# WSN.net
KiCad netlist of a schematic drawn in Altium Designer
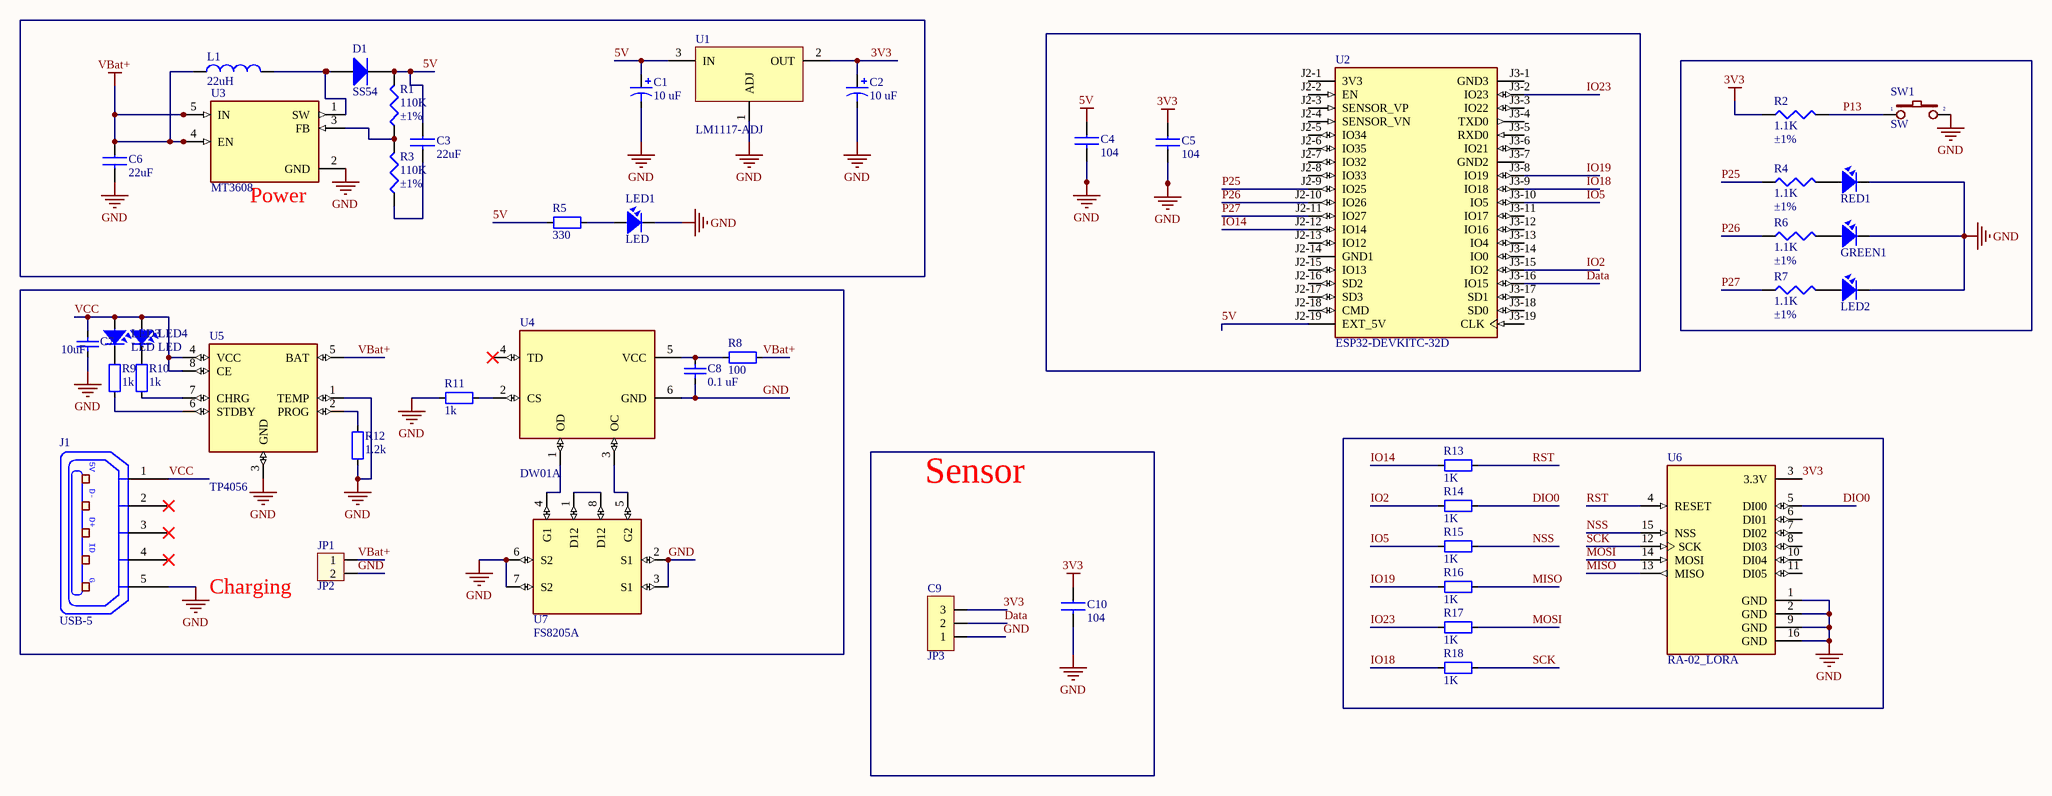
[diagram p0: WSN.SchDoc]

(export (version "E")
  (design (tool "Eeschema 10.0.6"))
  (components
    (comp (ref "C1")
      (value "10 uF")
      (footprint "C3MM")
      (description "Polarized Capacitor (Axial)")
      (fields (field (name "PUBLISHER") "Altium Limited"))
      (libsource (lib "My Library") (part "Cap Pol"))
    )
    (comp (ref "C2")
      (value "10 uF")
      (footprint "C3MM")
      (description "Polarized Capacitor (Axial)")
      (fields (field (name "PUBLISHER") "Altium Limited"))
      (libsource (lib "My Library") (part "Cap Pol"))
    )
    (comp (ref "C3")
      (value "22uF")
      (footprint "CAP0603")
      (description "CAP CER 30PF 50V NPO 0603")
      (fields
        (field (name "MANUFACTURER") "Yageo")
        (field (name "MANUFACTURER PART NUMBER") "CC0603JRNPO9BN300")
      )
      (libsource (lib "KhanhBK_SCH_Lib_6") (part "CC0603JRNPO9BN300"))
    )
    (comp (ref "C4")
      (value "104")
      (footprint "CAP0603")
      (description "CAP CER 30PF 50V NPO 0603")
      (fields
        (field (name "MANUFACTURER") "Yageo")
        (field (name "MANUFACTURER PART NUMBER") "CC0603JRNPO9BN300")
      )
      (libsource (lib "KhanhBK_SCH_Lib_6") (part "CC0603JRNPO9BN300"))
    )
    (comp (ref "C5")
      (value "104")
      (footprint "CAP0603")
      (description "CAP CER 30PF 50V NPO 0603")
      (fields
        (field (name "MANUFACTURER") "Yageo")
        (field (name "MANUFACTURER PART NUMBER") "CC0603JRNPO9BN300")
      )
      (libsource (lib "KhanhBK_SCH_Lib_6") (part "CC0603JRNPO9BN300"))
    )
    (comp (ref "C6")
      (value "22uF")
      (footprint "CAP0603")
      (description "CAP CER 30PF 50V NPO 0603")
      (fields
        (field (name "MANUFACTURER") "Yageo")
        (field (name "MANUFACTURER PART NUMBER") "CC0603JRNPO9BN300")
      )
      (libsource (lib "KhanhBK_SCH_Lib_6") (part "CC0603JRNPO9BN300"))
    )
    (comp (ref "C7")
      (value "10uF")
      (footprint "CAP_0805")
      (description "Capacitor")
      (fields (field (name "PUBLISHER") "Altium Limited"))
      (libsource (lib "My Library") (part "CapSMD"))
    )
    (comp (ref "C8")
      (value "0.1 uF")
      (footprint "CAP_0805")
      (description "Capacitor")
      (fields (field (name "PUBLISHER") "Altium Limited"))
      (libsource (lib "My Library") (part "CapSMD"))
    )
    (comp (ref "C9")
      (value "JP3")
      (footprint "JP3-C1T")
      (description "WR-PHD 2.54 mm Angled Socket Header")
      (fields
        (field (name "MANUFACTURER") "Würth Elektronik eiSos GmbH")
        (field (name "PARTNO") "613003143121")
        (field (name "CREATED BY") "Karrer Zheng")
      )
      (libsource (lib "KhanhBK_SCH_Library_1") (part "JP3"))
    )
    (comp (ref "C10")
      (value "104")
      (footprint "CAP0603")
      (description "CAP CER 30PF 50V NPO 0603")
      (fields
        (field (name "MANUFACTURER") "Yageo")
        (field (name "MANUFACTURER PART NUMBER") "CC0603JRNPO9BN300")
      )
      (libsource (lib "KhanhBK_SCH_Lib_6") (part "CC0603JRNPO9BN300"))
    )
    (comp (ref "D1")
      (value "SS54")
      (footprint "DIODE/POW/1A")
      (description "Diode Power")
      (fields (field (name "PUBLISHER") "Altium Limited"))
      (libsource (lib "Cty1") (part "Diode Power"))
    )
    (comp (ref "GREEN1")
      (value "LED")
      (footprint "LED-3MM-GREEN")
      (description "LED Single colour Green and Red")
      (libsource (lib "KhanhBK_SCH_Library_1") (part "LED"))
    )
    (comp (ref "J1")
      (value "USB-5")
      (footprint "USB-M1")
      (fields
        (field (name "MANUFACTURER") "FCI")
        (field (name "MANUFACTURER PART NUMBER") "10118193-0001LF")
        (field (name ".CREATOR") "MM")
        (field (name ".CHECKED PCB") "RF")
        (field (name ".CHECKED SCH") "MM")
      )
      (libsource (lib "My Library") (part "USB-5"))
    )
    (comp (ref "JP1")
      (value "JP2")
      (footprint "CON2")
      (description "Connector 2")
      (libsource (lib "My Library") (part "Con2"))
    )
    (comp (ref "L1")
      (value "22uH")
      (footprint "IND_400_500_212x114_SMD")
      (description "1mH Shielded Wirewound Inductor 600mA 1.82Ohm Max Nonstandard")
      (fields (field (name "MANUFACTURER") "Coilcraft") (field (name "MANUFACTURER PART NUMBER") "74477030"))
      (libsource (lib "Altium_Lib_by_KhueNguyenCreator") (part "IND_1mH-0.6A-20%-SMD"))
    )
    (comp (ref "LED1")
      (value "LED")
      (footprint "LED-0805-Red")
      (description "LED Single colour Green and Red")
      (libsource (lib "My Library") (part "LED"))
    )
    (comp (ref "LED2")
      (value "LED")
      (footprint "LED-3MM-YELLOW")
      (description "LED Single colour Green and Red")
      (libsource (lib "KhanhBK_SCH_Library_1") (part "LED"))
    )
    (comp (ref "LED3")
      (value "LED")
      (footprint "LED-0805-Green")
      (description "LED Single colour Green and Red")
      (libsource (lib "My Library") (part "LED"))
    )
    (comp (ref "LED4")
      (value "LED")
      (footprint "LED-0805-Red")
      (description "LED Single colour Green and Red")
      (libsource (lib "My Library") (part "LED"))
    )
    (comp (ref "R1")
      (value "110K")
      (footprint "RES0603")
      (description "RES SMD 1K OHM 1% 1/10W 0603")
      (fields
        (field (name "MANUFACTURER") "Yageo")
        (field (name "MANUFACTURER PART NUMBER") "RT0603FRD071KL")
        (field (name "TOLERANCE") "±1%")
      )
      (libsource (lib "KhanhBK_SCH_Lib_6") (part "RT0603FRD071KL"))
    )
    (comp (ref "R2")
      (value "1.1K")
      (footprint "RES0603")
      (description "RES SMD 1K OHM 1% 1/10W 0603")
      (fields
        (field (name "MANUFACTURER") "Yageo")
        (field (name "MANUFACTURER PART NUMBER") "RT0603FRD071KL")
        (field (name "TOLERANCE") "±1%")
      )
      (libsource (lib "KhanhBK_SCH_Lib_6") (part "RT0603FRD071KL"))
    )
    (comp (ref "R3")
      (value "110K")
      (footprint "RES0603")
      (description "RES SMD 1K OHM 1% 1/10W 0603")
      (fields
        (field (name "MANUFACTURER") "Yageo")
        (field (name "MANUFACTURER PART NUMBER") "RT0603FRD071KL")
        (field (name "TOLERANCE") "±1%")
      )
      (libsource (lib "KhanhBK_SCH_Lib_6") (part "RT0603FRD071KL"))
    )
    (comp (ref "R4")
      (value "1.1K")
      (footprint "RES0603")
      (description "RES SMD 1K OHM 1% 1/10W 0603")
      (fields
        (field (name "MANUFACTURER") "Yageo")
        (field (name "MANUFACTURER PART NUMBER") "RT0603FRD071KL")
        (field (name "TOLERANCE") "±1%")
      )
      (libsource (lib "KhanhBK_SCH_Lib_6") (part "RT0603FRD071KL"))
    )
    (comp (ref "R5")
      (value "330")
      (footprint "RES-SMD-0805")
      (description "Resistor")
      (fields
        (field (name "MANUFACTURER") "Generic Components")
        (field (name "PUBLISHER") "Altium Hobart Technology Centre")
      )
      (libsource (lib "My Library") (part "Resistor - SMD"))
    )
    (comp (ref "R6")
      (value "1.1K")
      (footprint "RES0603")
      (description "RES SMD 1K OHM 1% 1/10W 0603")
      (fields
        (field (name "MANUFACTURER") "Yageo")
        (field (name "MANUFACTURER PART NUMBER") "RT0603FRD071KL")
        (field (name "TOLERANCE") "±1%")
      )
      (libsource (lib "KhanhBK_SCH_Lib_6") (part "RT0603FRD071KL"))
    )
    (comp (ref "R7")
      (value "1.1K")
      (footprint "RES0603")
      (description "RES SMD 1K OHM 1% 1/10W 0603")
      (fields
        (field (name "MANUFACTURER") "Yageo")
        (field (name "MANUFACTURER PART NUMBER") "RT0603FRD071KL")
        (field (name "TOLERANCE") "±1%")
      )
      (libsource (lib "KhanhBK_SCH_Lib_6") (part "RT0603FRD071KL"))
    )
    (comp (ref "R8")
      (value "100")
      (footprint "RES-SMD-0805")
      (description "Resistor")
      (fields
        (field (name "MANUFACTURER") "Generic Components")
        (field (name "PUBLISHER") "Altium Hobart Technology Centre")
      )
      (libsource (lib "My Library") (part "Resistor - SMD"))
    )
    (comp (ref "R9")
      (value "1k")
      (footprint "RES-SMD-0805")
      (description "Resistor")
      (fields
        (field (name "MANUFACTURER") "Generic Components")
        (field (name "PUBLISHER") "Altium Hobart Technology Centre")
      )
      (libsource (lib "My Library") (part "Resistor - SMD"))
    )
    (comp (ref "R10")
      (value "1k")
      (footprint "RES-SMD-0805")
      (description "Resistor")
      (fields
        (field (name "MANUFACTURER") "Generic Components")
        (field (name "PUBLISHER") "Altium Hobart Technology Centre")
      )
      (libsource (lib "My Library") (part "Resistor - SMD"))
    )
    (comp (ref "R11")
      (value "1k")
      (footprint "RES-SMD-0805")
      (description "Resistor")
      (fields
        (field (name "MANUFACTURER") "Generic Components")
        (field (name "PUBLISHER") "Altium Hobart Technology Centre")
      )
      (libsource (lib "My Library") (part "Resistor - SMD"))
    )
    (comp (ref "R12")
      (value "1.2k")
      (footprint "RES-SMD-0805")
      (description "Resistor")
      (fields
        (field (name "MANUFACTURER") "Generic Components")
        (field (name "PUBLISHER") "Altium Hobart Technology Centre")
      )
      (libsource (lib "My Library") (part "Resistor - SMD"))
    )
    (comp (ref "R13")
      (value "1K")
      (footprint "RES-SMD-0805")
      (description "Resistor")
      (fields
        (field (name "MANUFACTURER") "Generic Components")
        (field (name "PUBLISHER") "Altium Hobart Technology Centre")
      )
      (libsource (lib "My Library") (part "Resistor - SMD"))
    )
    (comp (ref "R14")
      (value "1K")
      (footprint "RES-SMD-0805")
      (description "Resistor")
      (fields
        (field (name "MANUFACTURER") "Generic Components")
        (field (name "PUBLISHER") "Altium Hobart Technology Centre")
      )
      (libsource (lib "My Library") (part "Resistor - SMD"))
    )
    (comp (ref "R15")
      (value "1K")
      (footprint "RES-SMD-0805")
      (description "Resistor")
      (fields
        (field (name "MANUFACTURER") "Generic Components")
        (field (name "PUBLISHER") "Altium Hobart Technology Centre")
      )
      (libsource (lib "My Library") (part "Resistor - SMD"))
    )
    (comp (ref "R16")
      (value "1K")
      (footprint "RES-SMD-0805")
      (description "Resistor")
      (fields
        (field (name "MANUFACTURER") "Generic Components")
        (field (name "PUBLISHER") "Altium Hobart Technology Centre")
      )
      (libsource (lib "My Library") (part "Resistor - SMD"))
    )
    (comp (ref "R17")
      (value "1K")
      (footprint "RES-SMD-0805")
      (description "Resistor")
      (fields
        (field (name "MANUFACTURER") "Generic Components")
        (field (name "PUBLISHER") "Altium Hobart Technology Centre")
      )
      (libsource (lib "My Library") (part "Resistor - SMD"))
    )
    (comp (ref "R18")
      (value "1K")
      (footprint "RES-SMD-0805")
      (description "Resistor")
      (fields
        (field (name "MANUFACTURER") "Generic Components")
        (field (name "PUBLISHER") "Altium Hobart Technology Centre")
      )
      (libsource (lib "My Library") (part "Resistor - SMD"))
    )
    (comp (ref "RED1")
      (value "LED")
      (footprint "LED-3MM-RED")
      (description "LED Single colour Green and Red")
      (libsource (lib "KhanhBK_SCH_Library_1") (part "LED"))
    )
    (comp (ref "SW1")
      (value "SW")
      (footprint "SW1-SMD")
      (description "Switch button 2 pin")
      (libsource (lib "KhanhBK_SCH_Library_1") (part "SW2"))
    )
    (comp (ref "U1")
      (value "LM1117-ADJ")
      (footprint "LM1117-SOP")
      (description "800mA Low-Dropout Linear Regulator")
      (fields (field (name "CREATOR") "Nguyen Ba Bien"))
      (libsource (lib "My Library") (part "LM1117-ADJ"))
    )
    (comp (ref "U2")
      (value "ESP32-DEVKITC-32D")
      (footprint "MODULE_ESP32-DEVKITC-32D")
      (description "WiFi Development Tools (802.11) ESP32 General Development Kit, ESP32-WROOM-32D on the board")
      (fields (field (name "MF") "Espressif Systems"))
      (libsource (lib "ESP32-DEVKITC-32D") (part "ESP32-DEVKITC-32D"))
    )
    (comp (ref "U3")
      (value "MT3608")
      (footprint "SOT95P280X145-6N")
      (description "High Efficiency 1.2MHz2A Step Up Converter")
      (fields (field (name "MF") "Aerosemi Technology Co., Ltd"))
      (libsource (lib "MT3608") (part "MT3608"))
    )
    (comp (ref "U4")
      (value "DW01A")
      (footprint "SOT23-6")
      (description "One Cell Lithium-ion/Polymer Battery Protection IC")
      (libsource (lib "My Library") (part "DW01A"))
    )
    (comp (ref "U5")
      (value "TP4056")
      (footprint "TP4056")
      (description "Complete single cell Li-Ion battery with a constant current / constant voltage linear charger")
      (libsource (lib "My Library") (part "TP4056"))
    )
    (comp (ref "U6")
      (value "RA-02_LORA")
      (footprint "MODULE_RA-02_LORA")
      (description "Ra-02 LoRa RF M5Stack Platform Evaluation Expansion Board")
      (libsource (lib "RA-02_LORA (1)") (part "RA-02_LORA"))
    )
    (comp (ref "U7") (value "FS8205A") (footprint "FS8205A") (libsource (lib "My Library") (part "FS8205A")))
  )
  (nets
    (net (code "1") (name "/DIO0") (class "Default")
      (node (ref "R14") (pin "2") (pinfunction "2_2") (pintype "passive"))
      (node (ref "U6") (pin "5") (pinfunction "DI00_5") (pintype "bidirectional"))
    )
    (net (code "2") (name "/Data") (class "Default")
      (node (ref "C9") (pin "2") (pinfunction "2_2") (pintype "passive"))
      (node (ref "U2") (pin "J3-16") (pinfunction "IO15_J3-16") (pintype "bidirectional"))
    )
    (net (code "3") (name "/IO2") (class "Default")
      (node (ref "R14") (pin "1") (pinfunction "1_1") (pintype "passive"))
      (node (ref "U2") (pin "J3-15") (pinfunction "IO2_J3-15") (pintype "bidirectional"))
    )
    (net (code "4") (name "/IO5") (class "Default")
      (node (ref "R15") (pin "1") (pinfunction "1_1") (pintype "passive"))
      (node (ref "U2") (pin "J3-10") (pinfunction "IO5_J3-10") (pintype "bidirectional"))
    )
    (net (code "5") (name "/IO14") (class "Default")
      (node (ref "R13") (pin "1") (pinfunction "1_1") (pintype "passive"))
      (node (ref "U2") (pin "J2-12") (pinfunction "IO14_J2-12") (pintype "bidirectional"))
    )
    (net (code "6") (name "/IO18") (class "Default")
      (node (ref "R18") (pin "1") (pinfunction "1_1") (pintype "passive"))
      (node (ref "U2") (pin "J3-9") (pinfunction "IO18_J3-9") (pintype "bidirectional"))
    )
    (net (code "7") (name "/IO19") (class "Default")
      (node (ref "R16") (pin "1") (pinfunction "1_1") (pintype "passive"))
      (node (ref "U2") (pin "J3-8") (pinfunction "IO19_J3-8") (pintype "bidirectional"))
    )
    (net (code "8") (name "/IO23") (class "Default")
      (node (ref "R17") (pin "1") (pinfunction "1_1") (pintype "passive"))
      (node (ref "U2") (pin "J3-2") (pinfunction "IO23_J3-2") (pintype "bidirectional"))
    )
    (net (code "9") (name "/MISO") (class "Default")
      (node (ref "R16") (pin "2") (pinfunction "2_2") (pintype "passive"))
      (node (ref "U6") (pin "13") (pinfunction "MISO_13") (pintype "output"))
    )
    (net (code "10") (name "/MOSI") (class "Default")
      (node (ref "R17") (pin "2") (pinfunction "2_2") (pintype "passive"))
      (node (ref "U6") (pin "14") (pinfunction "MOSI_14") (pintype "input"))
    )
    (net (code "11") (name "/NSS") (class "Default")
      (node (ref "R15") (pin "2") (pinfunction "2_2") (pintype "passive"))
      (node (ref "U6") (pin "15") (pinfunction "NSS_15") (pintype "input"))
    )
    (net (code "12") (name "/P13") (class "Default")
      (node (ref "R2") (pin "2") (pinfunction "2_2") (pintype "passive"))
      (node (ref "SW1") (pin "1") (pinfunction "1_1") (pintype "passive"))
    )
    (net (code "13") (name "/P25") (class "Default")
      (node (ref "R4") (pin "1") (pinfunction "1_1") (pintype "passive"))
      (node (ref "U2") (pin "J2-9") (pinfunction "IO25_J2-9") (pintype "bidirectional"))
    )
    (net (code "14") (name "/P26") (class "Default")
      (node (ref "R6") (pin "1") (pinfunction "1_1") (pintype "passive"))
      (node (ref "U2") (pin "J2-10") (pinfunction "IO26_J2-10") (pintype "bidirectional"))
    )
    (net (code "15") (name "/P27") (class "Default")
      (node (ref "R7") (pin "1") (pinfunction "1_1") (pintype "passive"))
      (node (ref "U2") (pin "J2-11") (pinfunction "IO27_J2-11") (pintype "bidirectional"))
    )
    (net (code "16") (name "/RST") (class "Default")
      (node (ref "R13") (pin "2") (pinfunction "2_2") (pintype "passive"))
      (node (ref "U6") (pin "4") (pinfunction "RESET_4") (pintype "input"))
    )
    (net (code "17") (name "/SCK") (class "Default")
      (node (ref "R18") (pin "2") (pinfunction "2_2") (pintype "passive"))
      (node (ref "U6") (pin "12") (pinfunction "SCK_12") (pintype "input"))
    )
    (net (code "18") (name "/VCC") (class "Default")
      (node (ref "C7") (pin "2") (pinfunction "2_2") (pintype "passive"))
      (node (ref "J1") (pin "1") (pinfunction "P1_1") (pintype "passive"))
      (node (ref "LED3") (pin "1") (pinfunction "1_1") (pintype "passive"))
      (node (ref "LED4") (pin "1") (pinfunction "1_1") (pintype "passive"))
      (node (ref "U5") (pin "4") (pinfunction "VCC_4") (pintype "bidirectional"))
      (node (ref "U5") (pin "8") (pinfunction "CE_8") (pintype "bidirectional"))
    )
    (net (code "19") (name "3V3") (class "Default")
      (node (ref "C10") (pin "1") (pinfunction "1_1") (pintype "passive"))
      (node (ref "C2") (pin "1") (pinfunction "1_1") (pintype "passive"))
      (node (ref "C5") (pin "1") (pinfunction "1_1") (pintype "passive"))
      (node (ref "C9") (pin "3") (pinfunction "3_3") (pintype "passive"))
      (node (ref "R2") (pin "1") (pinfunction "1_1") (pintype "passive"))
      (node (ref "U1") (pin "2") (pinfunction "OUT_2") (pintype "passive"))
      (node (ref "U6") (pin "3") (pinfunction "3.3V_3") (pintype "power_in"))
    )
    (net (code "20") (name "5V") (class "Default")
      (node (ref "C1") (pin "1") (pinfunction "1_1") (pintype "passive"))
      (node (ref "C3") (pin "1") (pinfunction "1_1") (pintype "passive"))
      (node (ref "C4") (pin "1") (pinfunction "1_1") (pintype "passive"))
      (node (ref "D1") (pin "2") (pinfunction "K_2") (pintype "passive"))
      (node (ref "R1") (pin "2") (pinfunction "2_2") (pintype "passive"))
      (node (ref "R5") (pin "1") (pinfunction "1_1") (pintype "passive"))
      (node (ref "U1") (pin "3") (pinfunction "IN_3") (pintype "passive"))
      (node (ref "U2") (pin "J2-19") (pinfunction "EXT_5V_J2-19") (pintype "power_in"))
    )
    (net (code "21") (name "GND") (class "Default")
      (node (ref "C1") (pin "2") (pinfunction "2_2") (pintype "passive"))
      (node (ref "C10") (pin "2") (pinfunction "2_2") (pintype "passive"))
      (node (ref "C2") (pin "2") (pinfunction "2_2") (pintype "passive"))
      (node (ref "C4") (pin "2") (pinfunction "2_2") (pintype "passive"))
      (node (ref "C5") (pin "2") (pinfunction "2_2") (pintype "passive"))
      (node (ref "C6") (pin "2") (pinfunction "2_2") (pintype "passive"))
      (node (ref "C7") (pin "1") (pinfunction "1_1") (pintype "passive"))
      (node (ref "C8") (pin "1") (pinfunction "1_1") (pintype "passive"))
      (node (ref "C9") (pin "1") (pinfunction "1_1") (pintype "passive"))
      (node (ref "GREEN1") (pin "2") (pinfunction "2_2") (pintype "passive"))
      (node (ref "J1") (pin "5") (pinfunction "P5_5") (pintype "passive"))
      (node (ref "JP1") (pin "2") (pinfunction "2_2") (pintype "passive"))
      (node (ref "LED1") (pin "2") (pinfunction "2_2") (pintype "passive"))
      (node (ref "LED2") (pin "2") (pinfunction "2_2") (pintype "passive"))
      (node (ref "R11") (pin "1") (pinfunction "1_1") (pintype "passive"))
      (node (ref "R12") (pin "1") (pinfunction "1_1") (pintype "passive"))
      (node (ref "RED1") (pin "2") (pinfunction "2_2") (pintype "passive"))
      (node (ref "SW1") (pin "2") (pinfunction "2_2") (pintype "passive"))
      (node (ref "U1") (pin "1") (pinfunction "ADJ_1") (pintype "passive"))
      (node (ref "U3") (pin "2") (pinfunction "GND_2") (pintype "power_in"))
      (node (ref "U4") (pin "6") (pinfunction "GND_6") (pintype "power_in"))
      (node (ref "U5") (pin "1") (pinfunction "TEMP_1") (pintype "bidirectional"))
      (node (ref "U5") (pin "3") (pinfunction "GND_3") (pintype "bidirectional"))
      (node (ref "U6") (pin "1") (pinfunction "GND_1") (pintype "power_in"))
      (node (ref "U6") (pin "16") (pinfunction "GND_16") (pintype "power_in"))
      (node (ref "U6") (pin "2") (pinfunction "GND_2") (pintype "power_in"))
      (node (ref "U6") (pin "9") (pinfunction "GND_9") (pintype "power_in"))
      (node (ref "U7") (pin "2") (pinfunction "S1_2") (pintype "bidirectional"))
      (node (ref "U7") (pin "3") (pinfunction "S1_3") (pintype "bidirectional"))
      (node (ref "U7") (pin "6") (pinfunction "S2_6") (pintype "bidirectional"))
      (node (ref "U7") (pin "7") (pinfunction "S2_7") (pintype "bidirectional"))
    )
    (net (code "22") (name "Net-(C3-Pad2)") (class "Default")
      (node (ref "C3") (pin "2") (pinfunction "2_2") (pintype "passive"))
      (node (ref "R3") (pin "1") (pinfunction "1_1") (pintype "passive"))
    )
    (net (code "23") (name "Net-(D1-A)") (class "Default")
      (node (ref "D1") (pin "1") (pinfunction "A_1") (pintype "passive"))
      (node (ref "L1") (pin "2") (pinfunction "2_2") (pintype "passive"))
      (node (ref "U3") (pin "1") (pinfunction "SW_1") (pintype "output"))
    )
    (net (code "24") (name "Net-(GREEN1-Pad1)") (class "Default")
      (node (ref "GREEN1") (pin "1") (pinfunction "1_1") (pintype "passive"))
      (node (ref "R6") (pin "2") (pinfunction "2_2") (pintype "passive"))
    )
    (net (code "25") (name "Net-(LED1-Pad1)") (class "Default")
      (node (ref "LED1") (pin "1") (pinfunction "1_1") (pintype "passive"))
      (node (ref "R5") (pin "2") (pinfunction "2_2") (pintype "passive"))
    )
    (net (code "26") (name "Net-(LED2-Pad1)") (class "Default")
      (node (ref "LED2") (pin "1") (pinfunction "1_1") (pintype "passive"))
      (node (ref "R7") (pin "2") (pinfunction "2_2") (pintype "passive"))
    )
    (net (code "27") (name "Net-(LED3-Pad2)") (class "Default")
      (node (ref "LED3") (pin "2") (pinfunction "2_2") (pintype "passive"))
      (node (ref "R9") (pin "2") (pinfunction "2_2") (pintype "passive"))
    )
    (net (code "28") (name "Net-(LED4-Pad2)") (class "Default")
      (node (ref "LED4") (pin "2") (pinfunction "2_2") (pintype "passive"))
      (node (ref "R10") (pin "2") (pinfunction "2_2") (pintype "passive"))
    )
    (net (code "29") (name "Net-(R4-Pad2)") (class "Default")
      (node (ref "R4") (pin "2") (pinfunction "2_2") (pintype "passive"))
      (node (ref "RED1") (pin "1") (pinfunction "1_1") (pintype "passive"))
    )
    (net (code "30") (name "Net-(U3-FB)") (class "Default")
      (node (ref "R1") (pin "1") (pinfunction "1_1") (pintype "passive"))
      (node (ref "R3") (pin "2") (pinfunction "2_2") (pintype "passive"))
      (node (ref "U3") (pin "3") (pinfunction "FB_3") (pintype "input"))
    )
    (net (code "31") (name "Net-(U4-CS)") (class "Default")
      (node (ref "R11") (pin "2") (pinfunction "2_2") (pintype "passive"))
      (node (ref "U4") (pin "2") (pinfunction "CS_2") (pintype "bidirectional"))
    )
    (net (code "32") (name "Net-(U4-OC)") (class "Default")
      (node (ref "U4") (pin "3") (pinfunction "OC_3") (pintype "bidirectional"))
      (node (ref "U7") (pin "5") (pinfunction "G2_5") (pintype "bidirectional"))
    )
    (net (code "33") (name "Net-(U4-OD)") (class "Default")
      (node (ref "U4") (pin "1") (pinfunction "OD_1") (pintype "bidirectional"))
      (node (ref "U7") (pin "4") (pinfunction "G1_4") (pintype "bidirectional"))
    )
    (net (code "34") (name "Net-(U4-VCC)") (class "Default")
      (node (ref "C8") (pin "2") (pinfunction "2_2") (pintype "passive"))
      (node (ref "R8") (pin "1") (pinfunction "1_1") (pintype "passive"))
      (node (ref "U4") (pin "5") (pinfunction "VCC_5") (pintype "power_in"))
    )
    (net (code "35") (name "Net-(U5-CHRG)") (class "Default")
      (node (ref "R10") (pin "1") (pinfunction "1_1") (pintype "passive"))
      (node (ref "U5") (pin "7") (pinfunction "CHRG_7") (pintype "bidirectional"))
    )
    (net (code "36") (name "Net-(U5-PROG)") (class "Default")
      (node (ref "R12") (pin "2") (pinfunction "2_2") (pintype "passive"))
      (node (ref "U5") (pin "2") (pinfunction "PROG_2") (pintype "bidirectional"))
    )
    (net (code "37") (name "Net-(U5-STDBY)") (class "Default")
      (node (ref "R9") (pin "1") (pinfunction "1_1") (pintype "passive"))
      (node (ref "U5") (pin "6") (pinfunction "STDBY_6") (pintype "bidirectional"))
    )
    (net (code "38") (name "Net-(U7-D12-Pad1)") (class "Default")
      (node (ref "U7") (pin "1") (pinfunction "D12_1") (pintype "bidirectional"))
      (node (ref "U7") (pin "8") (pinfunction "D12_8") (pintype "bidirectional"))
    )
    (net (code "39") (name "VBat+") (class "Default")
      (node (ref "C6") (pin "1") (pinfunction "1_1") (pintype "passive"))
      (node (ref "JP1") (pin "1") (pinfunction "1_1") (pintype "passive"))
      (node (ref "L1") (pin "1") (pinfunction "1_1") (pintype "passive"))
      (node (ref "R8") (pin "2") (pinfunction "2_2") (pintype "passive"))
      (node (ref "U3") (pin "4") (pinfunction "EN_4") (pintype "input"))
      (node (ref "U3") (pin "5") (pinfunction "IN_5") (pintype "input"))
      (node (ref "U5") (pin "5") (pinfunction "BAT_5") (pintype "bidirectional"))
    )
    (net (code "40") (name "unconnected-(J1-P2-Pad2)") (class "Default")
      (node (ref "J1") (pin "2") (pinfunction "P2_2") (pintype "passive+no_connect"))
    )
    (net (code "41") (name "unconnected-(J1-P3-Pad3)") (class "Default")
      (node (ref "J1") (pin "3") (pinfunction "P3_3") (pintype "passive+no_connect"))
    )
    (net (code "42") (name "unconnected-(J1-P4-Pad4)") (class "Default")
      (node (ref "J1") (pin "4") (pinfunction "P4_4") (pintype "passive+no_connect"))
    )
    (net (code "43") (name "unconnected-(U2-3V3-PadJ2-1)") (class "Default")
      (node (ref "U2") (pin "J2-1") (pinfunction "3V3_J2-1") (pintype "power_in"))
    )
    (net (code "44") (name "unconnected-(U2-CLK-PadJ3-19)") (class "Default")
      (node (ref "U2") (pin "J3-19") (pinfunction "CLK_J3-19") (pintype "input"))
    )
    (net (code "45") (name "unconnected-(U2-CMD-PadJ2-18)") (class "Default")
      (node (ref "U2") (pin "J2-18") (pinfunction "CMD_J2-18") (pintype "bidirectional"))
    )
    (net (code "46") (name "unconnected-(U2-EN-PadJ2-2)") (class "Default")
      (node (ref "U2") (pin "J2-2") (pinfunction "EN_J2-2") (pintype "input"))
    )
    (net (code "47") (name "unconnected-(U2-GND1-PadJ2-14)") (class "Default")
      (node (ref "U2") (pin "J2-14") (pinfunction "GND1_J2-14") (pintype "power_in"))
    )
    (net (code "48") (name "unconnected-(U2-GND2-PadJ3-7)") (class "Default")
      (node (ref "U2") (pin "J3-7") (pinfunction "GND2_J3-7") (pintype "power_in"))
    )
    (net (code "49") (name "unconnected-(U2-GND3-PadJ3-1)") (class "Default")
      (node (ref "U2") (pin "J3-1") (pinfunction "GND3_J3-1") (pintype "power_in"))
    )
    (net (code "50") (name "unconnected-(U2-IO0-PadJ3-14)") (class "Default")
      (node (ref "U2") (pin "J3-14") (pinfunction "IO0_J3-14") (pintype "bidirectional"))
    )
    (net (code "51") (name "unconnected-(U2-IO4-PadJ3-13)") (class "Default")
      (node (ref "U2") (pin "J3-13") (pinfunction "IO4_J3-13") (pintype "bidirectional"))
    )
    (net (code "52") (name "unconnected-(U2-IO12-PadJ2-13)") (class "Default")
      (node (ref "U2") (pin "J2-13") (pinfunction "IO12_J2-13") (pintype "bidirectional"))
    )
    (net (code "53") (name "unconnected-(U2-IO13-PadJ2-15)") (class "Default")
      (node (ref "U2") (pin "J2-15") (pinfunction "IO13_J2-15") (pintype "bidirectional"))
    )
    (net (code "54") (name "unconnected-(U2-IO16-PadJ3-12)") (class "Default")
      (node (ref "U2") (pin "J3-12") (pinfunction "IO16_J3-12") (pintype "bidirectional"))
    )
    (net (code "55") (name "unconnected-(U2-IO17-PadJ3-11)") (class "Default")
      (node (ref "U2") (pin "J3-11") (pinfunction "IO17_J3-11") (pintype "bidirectional"))
    )
    (net (code "56") (name "unconnected-(U2-IO21-PadJ3-6)") (class "Default")
      (node (ref "U2") (pin "J3-6") (pinfunction "IO21_J3-6") (pintype "bidirectional"))
    )
    (net (code "57") (name "unconnected-(U2-IO22-PadJ3-3)") (class "Default")
      (node (ref "U2") (pin "J3-3") (pinfunction "IO22_J3-3") (pintype "bidirectional"))
    )
    (net (code "58") (name "unconnected-(U2-IO32-PadJ2-7)") (class "Default")
      (node (ref "U2") (pin "J2-7") (pinfunction "IO32_J2-7") (pintype "bidirectional"))
    )
    (net (code "59") (name "unconnected-(U2-IO33-PadJ2-8)") (class "Default")
      (node (ref "U2") (pin "J2-8") (pinfunction "IO33_J2-8") (pintype "bidirectional"))
    )
    (net (code "60") (name "unconnected-(U2-IO34-PadJ2-5)") (class "Default")
      (node (ref "U2") (pin "J2-5") (pinfunction "IO34_J2-5") (pintype "bidirectional"))
    )
    (net (code "61") (name "unconnected-(U2-IO35-PadJ2-6)") (class "Default")
      (node (ref "U2") (pin "J2-6") (pinfunction "IO35_J2-6") (pintype "bidirectional"))
    )
    (net (code "62") (name "unconnected-(U2-RXD0-PadJ3-5)") (class "Default")
      (node (ref "U2") (pin "J3-5") (pinfunction "RXD0_J3-5") (pintype "input"))
    )
    (net (code "63") (name "unconnected-(U2-SD0-PadJ3-18)") (class "Default")
      (node (ref "U2") (pin "J3-18") (pinfunction "SD0_J3-18") (pintype "bidirectional"))
    )
    (net (code "64") (name "unconnected-(U2-SD1-PadJ3-17)") (class "Default")
      (node (ref "U2") (pin "J3-17") (pinfunction "SD1_J3-17") (pintype "bidirectional"))
    )
    (net (code "65") (name "unconnected-(U2-SD2-PadJ2-16)") (class "Default")
      (node (ref "U2") (pin "J2-16") (pinfunction "SD2_J2-16") (pintype "bidirectional"))
    )
    (net (code "66") (name "unconnected-(U2-SD3-PadJ2-17)") (class "Default")
      (node (ref "U2") (pin "J2-17") (pinfunction "SD3_J2-17") (pintype "bidirectional"))
    )
    (net (code "67") (name "unconnected-(U2-SENSOR_VN-PadJ2-4)") (class "Default")
      (node (ref "U2") (pin "J2-4") (pinfunction "SENSOR_VN_J2-4") (pintype "input"))
    )
    (net (code "68") (name "unconnected-(U2-SENSOR_VP-PadJ2-3)") (class "Default")
      (node (ref "U2") (pin "J2-3") (pinfunction "SENSOR_VP_J2-3") (pintype "input"))
    )
    (net (code "69") (name "unconnected-(U2-TXD0-PadJ3-4)") (class "Default")
      (node (ref "U2") (pin "J3-4") (pinfunction "TXD0_J3-4") (pintype "output"))
    )
    (net (code "70") (name "unconnected-(U4-TD-Pad4)") (class "Default")
      (node (ref "U4") (pin "4") (pinfunction "TD_4") (pintype "bidirectional+no_connect"))
    )
    (net (code "71") (name "unconnected-(U6-DI01-Pad6)") (class "Default")
      (node (ref "U6") (pin "6") (pinfunction "DI01_6") (pintype "bidirectional"))
    )
    (net (code "72") (name "unconnected-(U6-DI02-Pad7)") (class "Default")
      (node (ref "U6") (pin "7") (pinfunction "DI02_7") (pintype "bidirectional"))
    )
    (net (code "73") (name "unconnected-(U6-DI03-Pad8)") (class "Default")
      (node (ref "U6") (pin "8") (pinfunction "DI03_8") (pintype "bidirectional"))
    )
    (net (code "74") (name "unconnected-(U6-DI04-Pad10)") (class "Default")
      (node (ref "U6") (pin "10") (pinfunction "DI04_10") (pintype "bidirectional"))
    )
    (net (code "75") (name "unconnected-(U6-DI05-Pad11)") (class "Default")
      (node (ref "U6") (pin "11") (pinfunction "DI05_11") (pintype "bidirectional"))
    )
  )
)
